# Power.net
KiCad netlist of a schematic drawn in Altium Designer
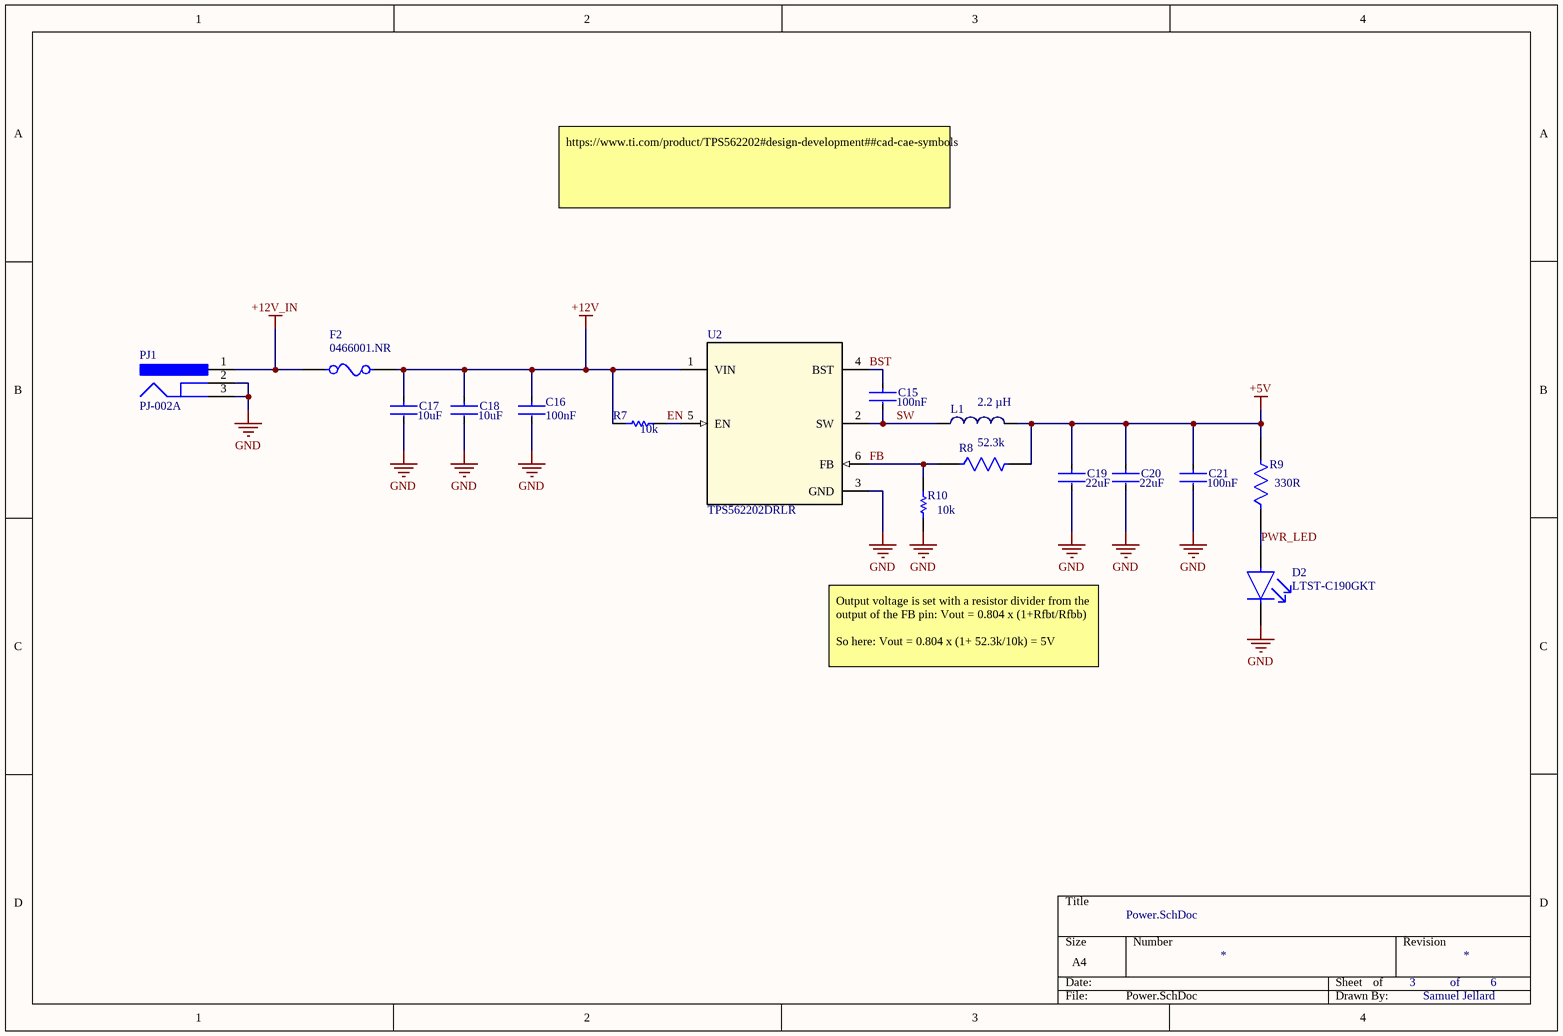
[diagram p0: Power.SchDoc]

(export (version "E")
  (design (tool "Eeschema 10.0.6"))
  (components
    (comp (ref "C15")
      (value "C1608X7R1E104K080AA")
      (footprint "FP-C1608-080-0_1-IPC_B")
      (description "Multilayer Ceramic Capacitors 100nF ±10% 25V X7R SMD 0603")
      (fields
        (field (name "TOLERANCE") "10%")
        (field (name "CAPACITANCE") "100nF")
        (field (name "VOLTAGE") "25V")
      )
      (libsource (lib "Altium Content Vault") (part "236180d848d6139a670b325ea6854c9"))
    )
    (comp (ref "C16")
      (value "C1608X7R1E104K080AA")
      (footprint "FP-C1608-080-0_1-IPC_B")
      (description "Multilayer Ceramic Capacitors 100nF ±10% 25V X7R SMD 0603")
      (fields
        (field (name "TOLERANCE") "10%")
        (field (name "CAPACITANCE") "100nF")
        (field (name "VOLTAGE") "25V")
      )
      (libsource (lib "Altium Content Vault") (part "236180d848d6139a670b325ea6854c9"))
    )
    (comp (ref "C17")
      (value "GRM21BR61E106MA73L")
      (footprint "FP-GRM21B-0_15-IPC_A")
      (description "Chip Multilayer Ceramic Capacitors for General Purpose, 0805, 10uF, X5R, 15%, 20%, 25V")
      (fields (field (name "TOLERANCE") "20%") (field (name "CAPACITANCE") "10uF"))
      (libsource (lib "Altium Content Vault") (part "b4654b650e69147ec39a6b967a45e02"))
    )
    (comp (ref "C18")
      (value "GRM21BR61E106MA73L")
      (footprint "FP-GRM21B-0_15-IPC_A")
      (description "Chip Multilayer Ceramic Capacitors for General Purpose, 0805, 10uF, X5R, 15%, 20%, 25V")
      (fields (field (name "TOLERANCE") "20%") (field (name "CAPACITANCE") "10uF"))
      (libsource (lib "Altium Content Vault") (part "b4654b650e69147ec39a6b967a45e02"))
    )
    (comp (ref "C19")
      (value "GRM21BR61A226ME44")
      (footprint "FP-GRM21B-0_2-e0_2_0_7-IPC_C")
      (description "Chip Multilayer Ceramic Capacitors for General Purpose, 0805, 22uF, X5R, 15%, 20%, 10V")
      (fields
        (field (name "TOLERANCE") "20%")
        (field (name "VOLTAGE") "10V")
        (field (name "CAPACITANCE") "22uF")
      )
      (libsource (lib "Altium Content Vault") (part "b4654b650e69147ec39a6b967a45e02"))
    )
    (comp (ref "C20")
      (value "GRM21BR61A226ME44")
      (footprint "FP-GRM21B-0_2-e0_2_0_7-IPC_C")
      (description "Chip Multilayer Ceramic Capacitors for General Purpose, 0805, 22uF, X5R, 15%, 20%, 10V")
      (fields
        (field (name "TOLERANCE") "20%")
        (field (name "VOLTAGE") "10V")
        (field (name "CAPACITANCE") "22uF")
      )
      (libsource (lib "Altium Content Vault") (part "b4654b650e69147ec39a6b967a45e02"))
    )
    (comp (ref "C21")
      (value "C1608X7R1E104K080AA")
      (footprint "FP-C1608-080-0_1-IPC_B")
      (description "Multilayer Ceramic Capacitors 100nF ±10% 25V X7R SMD 0603")
      (fields
        (field (name "TOLERANCE") "10%")
        (field (name "CAPACITANCE") "100nF")
        (field (name "VOLTAGE") "25V")
      )
      (libsource (lib "Altium Content Vault") (part "236180d848d6139a670b325ea6854c9"))
    )
    (comp (ref "D2")
      (value "LTST-C190GKT")
      (footprint "FP-LTST-C190GKT-MFG")
      (description "LED Uni-Color Green 565nm 2-Pin Chip LED T/R")
      (fields (field (name "VOLTAGE") "2V"))
      (libsource (lib "Altium Content Vault") (part "8706943c75ba83719d021d2fdc84c58"))
    )
    (comp (ref "F2")
      (value "0466001.NR")
      (footprint "FP-0466-MFG")
      (description "FUSE BOARD MNT 1A 63VAC/VDC 1206")
      (fields
        (field (name "MANUFACTURER") "Littelfuse Inc")
        (field (name "OCTOPART") "https://octopart.com/0466001.nr-littelfuse-566005")
      )
      (libsource (lib "Altium Content Vault") (part "5bcf9b9f640e542cf0359d10258e979"))
    )
    (comp (ref "L1")
      (value "74437349022")
      (footprint "WE-LHMI 7050")
      (description "SMD Power Inductor WE-LHMI, L=2.2 µH")
      (fields (field (name "INDUCTANCE") "2.2 µH") (field (name "MANUFACTURER") "Wuerth Elektronik"))
      (libsource (lib "Altium Content Vault") (part "WE-IND-INDUCTOR-2"))
    )
    (comp (ref "PJ1")
      (value "PJ-002A")
      (footprint "CUI-PJ-002A_V")
      (fields (field (name "MANUFACTURER") "CUIInc."))
      (libsource (lib "Altium Content Vault") (part "JACK-2CD3-RN"))
    )
    (comp (ref "R7")
      (value "CRCW060310K0FKEA")
      (footprint "RESC1609X50X30NL8T20")
      (description "Chip Resistor, 10 KOhm, +/- 1%, 100 mW, -55 to 155 degC, 0603 (1608 Metric), RoHS, Tape and Reel")
      (fields (field (name "MANUFACTURER") "Vishay Semiconductor"))
      (libsource (lib "Altium Content Vault") (part "RES-2"))
    )
    (comp (ref "R8")
      (value "CRCW060352K3FKEA")
      (footprint "FP-CRCW0603-e3-IPC_B")
      (description "RES Thick Film, 52.3kΩ, 1%, 0.1W, 100ppm/°C, 0603")
      (fields (field (name "TOLERANCE") "1%"))
      (libsource (lib "Altium Content Vault") (part "1029c3af85768c4190bb7ad29bc67b5"))
    )
    (comp (ref "R9")
      (value "CRCW0603330RFKEA")
      (footprint "FP-CRCW0603-e3-IPC_B")
      (description "RES Thick Film, 330Ω, 1%, 0.1W, 100ppm/°C, 0603")
      (fields (field (name "TOLERANCE") "1%") (field (name "RESISTANCE") "330R"))
      (libsource (lib "Altium Content Vault") (part "1029c3af85768c4190bb7ad29bc67b5"))
    )
    (comp (ref "R10")
      (value "CRCW060310K0FKEA")
      (footprint "RESC1609X50X30NL8T20")
      (description "Chip Resistor, 10 KOhm, +/- 1%, 100 mW, -55 to 155 degC, 0603 (1608 Metric), RoHS, Tape and Reel")
      (fields (field (name "MANUFACTURER") "Vishay Semiconductor"))
      (libsource (lib "Altium Content Vault") (part "RES-2"))
    )
    (comp (ref "U2")
      (value "TPS562202DRLR")
      (footprint "TPS562202DRLR:DRL0006A")
      (fields (field (name "COPYRIGHT") "Copyright (C) 2021 Ultra Librarian. All rights reserved."))
      (libsource (lib "TPS562202DRLR") (part "TPS562202DRLR"))
    )
  )
  (nets
    (net (code "1") (name "+5V") (class "Default")
      (node (ref "C19") (pin "1") (pinfunction "1_1") (pintype "passive"))
      (node (ref "C20") (pin "1") (pinfunction "1_1") (pintype "passive"))
      (node (ref "C21") (pin "2") (pinfunction "2_2") (pintype "passive"))
      (node (ref "L1") (pin "2") (pinfunction "2_2") (pintype "passive"))
      (node (ref "R8") (pin "2") (pinfunction "2_2") (pintype "passive"))
      (node (ref "R9") (pin "2") (pinfunction "2_2") (pintype "passive"))
    )
    (net (code "2") (name "+12V") (class "Default")
      (node (ref "C16") (pin "2") (pinfunction "2_2") (pintype "passive"))
      (node (ref "C17") (pin "1") (pinfunction "1_1") (pintype "passive"))
      (node (ref "C18") (pin "1") (pinfunction "1_1") (pintype "passive"))
      (node (ref "F2") (pin "2") (pinfunction "2_2") (pintype "passive"))
      (node (ref "R7") (pin "1") (pinfunction "1_1") (pintype "passive"))
      (node (ref "U2") (pin "1") (pinfunction "VIN_1") (pintype "power_in"))
    )
    (net (code "3") (name "+12V_IN") (class "Default")
      (node (ref "F2") (pin "1") (pinfunction "1_1") (pintype "passive"))
      (node (ref "PJ1") (pin "1") (pinfunction "1_1") (pintype "passive"))
    )
    (net (code "4") (name "/BST") (class "Default")
      (node (ref "C15") (pin "2") (pinfunction "2_2") (pintype "passive"))
      (node (ref "U2") (pin "4") (pinfunction "BST_4") (pintype "passive"))
    )
    (net (code "5") (name "/EN") (class "Default")
      (node (ref "R7") (pin "2") (pinfunction "2_2") (pintype "passive"))
      (node (ref "U2") (pin "5") (pinfunction "EN_5") (pintype "input"))
    )
    (net (code "6") (name "/FB") (class "Default")
      (node (ref "R10") (pin "2") (pinfunction "2_2") (pintype "passive"))
      (node (ref "R8") (pin "1") (pinfunction "1_1") (pintype "passive"))
      (node (ref "U2") (pin "6") (pinfunction "FB_6") (pintype "input"))
    )
    (net (code "7") (name "/PWR_LED") (class "Default")
      (node (ref "D2") (pin "2") (pinfunction "A_2") (pintype "passive"))
      (node (ref "R9") (pin "1") (pinfunction "1_1") (pintype "passive"))
    )
    (net (code "8") (name "/SW") (class "Default")
      (node (ref "C15") (pin "1") (pinfunction "1_1") (pintype "passive"))
      (node (ref "L1") (pin "1") (pinfunction "1_1") (pintype "passive"))
      (node (ref "U2") (pin "2") (pinfunction "SW_2") (pintype "power_in"))
    )
    (net (code "9") (name "GND") (class "Default")
      (node (ref "C16") (pin "1") (pinfunction "1_1") (pintype "passive"))
      (node (ref "C17") (pin "2") (pinfunction "2_2") (pintype "passive"))
      (node (ref "C18") (pin "2") (pinfunction "2_2") (pintype "passive"))
      (node (ref "C19") (pin "2") (pinfunction "2_2") (pintype "passive"))
      (node (ref "C20") (pin "2") (pinfunction "2_2") (pintype "passive"))
      (node (ref "C21") (pin "1") (pinfunction "1_1") (pintype "passive"))
      (node (ref "D2") (pin "1") (pinfunction "C_1") (pintype "passive"))
      (node (ref "PJ1") (pin "2") (pinfunction "2_2") (pintype "passive"))
      (node (ref "PJ1") (pin "3") (pinfunction "3_3") (pintype "passive"))
      (node (ref "R10") (pin "1") (pinfunction "1_1") (pintype "passive"))
      (node (ref "U2") (pin "3") (pinfunction "GND_3") (pintype "power_in"))
    )
  )
)
